# RF_TRANSMITTER_Schematic.net
KiCad netlist of a schematic drawn in Altium Designer
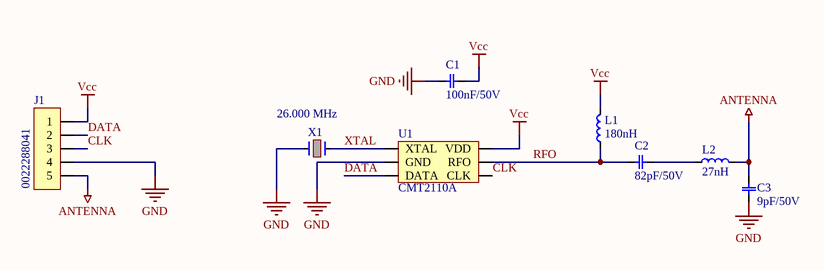
[diagram p0: RF_TRANSMITTER_Schematic.SchDoc]

(export (version "E")
  (design (tool "Eeschema 10.0.6"))
  (components
    (comp (ref "C1")
      (value "100nF/50V")
      (footprint "Cap_0805")
      (description "CAP CER nF 100 50V X7R 0805")
      (fields
        (field (name "MANUFACTURER") "TDK Corporation")
        (field (name "MANUFACTURER PART NUMBER") "C2012X7R1H104K125AE")
      )
      (libsource (lib "SEMATIK_LIB") (part "C2012X7R1H104K125AE"))
    )
    (comp (ref "C2")
      (value "82pF/50V")
      (footprint "Cap_0805")
      (description "CAP CER pF 82 50V C0G/NPO 0805")
      (fields
        (field (name "MANUFACTURER") "Yageo")
        (field (name "MANUFACTURER PART NUMBER") "CC0805JRNPO9BN820")
      )
      (libsource (lib "SEMATIK_LIB") (part "CC0805JRNPO9BN820"))
    )
    (comp (ref "C3")
      (value "9pF/50V")
      (footprint "Cap_0805")
      (description "CAP CER pF 9 50V C0G/NPO 0805")
      (fields
        (field (name "MANUFACTURER") "Yageo")
        (field (name "MANUFACTURER PART NUMBER") "CC0805DRNPO9BN9R0")
      )
      (libsource (lib "SEMATIK_LIB") (part "CC0805DRNPO9BN9R0"))
    )
    (comp (ref "J1")
      (value "0022288041")
      (footprint "HDR_MALE_1x5_100mil_90DRC")
      (description "CONN HEADER 4POS 2.54MM R/A")
      (fields (field (name "MANUFACTURER") "Molex"))
      (libsource (lib "SEMATIK_LIB") (part "0022288041"))
    )
    (comp (ref "L1")
      (value "180nH")
      (footprint "FERRITEBEAD_0805")
      (description "FIXED IND nH 180 300MA 250MOHM SM")
      (fields
        (field (name "MANUFACTURER") "TDK")
        (field (name "MANUFACTURER PART NUMBER") "MLF2012DR18KTD25")
      )
      (libsource (lib "SEMATIK_LIB") (part "MLF2012DR18KTD25"))
    )
    (comp (ref "L2")
      (value "27nH")
      (footprint "FERRITEBEAD_0805")
      (description "FIXED IND nH 27 600MA 120MOHM SMD")
      (fields
        (field (name "MANUFACTURER") "Johanson")
        (field (name "MANUFACTURER PART NUMBER") "L-15W27NJV4E")
      )
      (libsource (lib "SEMATIK_LIB") (part "L-15W27NJV4E"))
    )
    (comp (ref "U1")
      (value "CMT2110A")
      (footprint "SOT-23-6")
      (description "RF TRANSMITTER IC ASK/OOK 300-960MHZ SOT23-6 SMD")
      (libsource (lib "SEMATIK_LIB") (part "CMT2110A-ESR"))
    )
    (comp (ref "X1")
      (value "26.000 MHz")
      (footprint "HC-49/US")
      (description "CRYSTAL 26.0000MHZ 18PF TH")
      (fields (field (name "MANUFACTURER") "TXC") (field (name "MANUFACTURER PART NUMBER") "9B-26.000MAAJ-B"))
      (libsource (lib "SEMATIK_LIB") (part "9B-26.000MAAJ-B"))
    )
  )
  (nets
    (net (code "1") (name "/CLK") (class "Default")
      (node (ref "J1") (pin "3") (pinfunction "3_3") (pintype "passive"))
      (node (ref "U1") (pin "4") (pinfunction "CLK_4") (pintype "passive"))
    )
    (net (code "2") (name "/DATA") (class "Default")
      (node (ref "J1") (pin "2") (pinfunction "2_2") (pintype "passive"))
      (node (ref "U1") (pin "3") (pinfunction "DATA_3") (pintype "passive"))
    )
    (net (code "3") (name "/RFO") (class "Default")
      (node (ref "C2") (pin "2") (pinfunction "2_2") (pintype "passive"))
      (node (ref "L1") (pin "1") (pinfunction "1_1") (pintype "passive"))
      (node (ref "U1") (pin "5") (pinfunction "RFO_5") (pintype "passive"))
    )
    (net (code "4") (name "/XTAL") (class "Default")
      (node (ref "U1") (pin "1") (pinfunction "XTAL_1") (pintype "passive"))
      (node (ref "X1") (pin "2") (pinfunction "2_2") (pintype "passive"))
    )
    (net (code "5") (name "ANTENNA") (class "Default")
      (node (ref "C3") (pin "2") (pinfunction "2_2") (pintype "passive"))
      (node (ref "J1") (pin "5") (pinfunction "5_5") (pintype "passive"))
      (node (ref "L2") (pin "2") (pinfunction "2_2") (pintype "passive"))
    )
    (net (code "6") (name "GND") (class "Default")
      (node (ref "C1") (pin "1") (pinfunction "1_1") (pintype "passive"))
      (node (ref "C3") (pin "1") (pinfunction "1_1") (pintype "passive"))
      (node (ref "J1") (pin "4") (pinfunction "4_4") (pintype "passive"))
      (node (ref "U1") (pin "2") (pinfunction "GND_2") (pintype "passive"))
      (node (ref "X1") (pin "1") (pinfunction "1_1") (pintype "passive"))
    )
    (net (code "7") (name "Net-(C2-Pad1)") (class "Default")
      (node (ref "C2") (pin "1") (pinfunction "1_1") (pintype "passive"))
      (node (ref "L2") (pin "1") (pinfunction "1_1") (pintype "passive"))
    )
    (net (code "8") (name "Vcc") (class "Default")
      (node (ref "C1") (pin "2") (pinfunction "2_2") (pintype "passive"))
      (node (ref "J1") (pin "1") (pinfunction "1_1") (pintype "passive"))
      (node (ref "L1") (pin "2") (pinfunction "2_2") (pintype "passive"))
      (node (ref "U1") (pin "6") (pinfunction "VDD_6") (pintype "passive"))
    )
  )
)
